# EEZ_DIB_MUX14D_r1B2.net
KiCad netlist of a schematic drawn in EAGLE
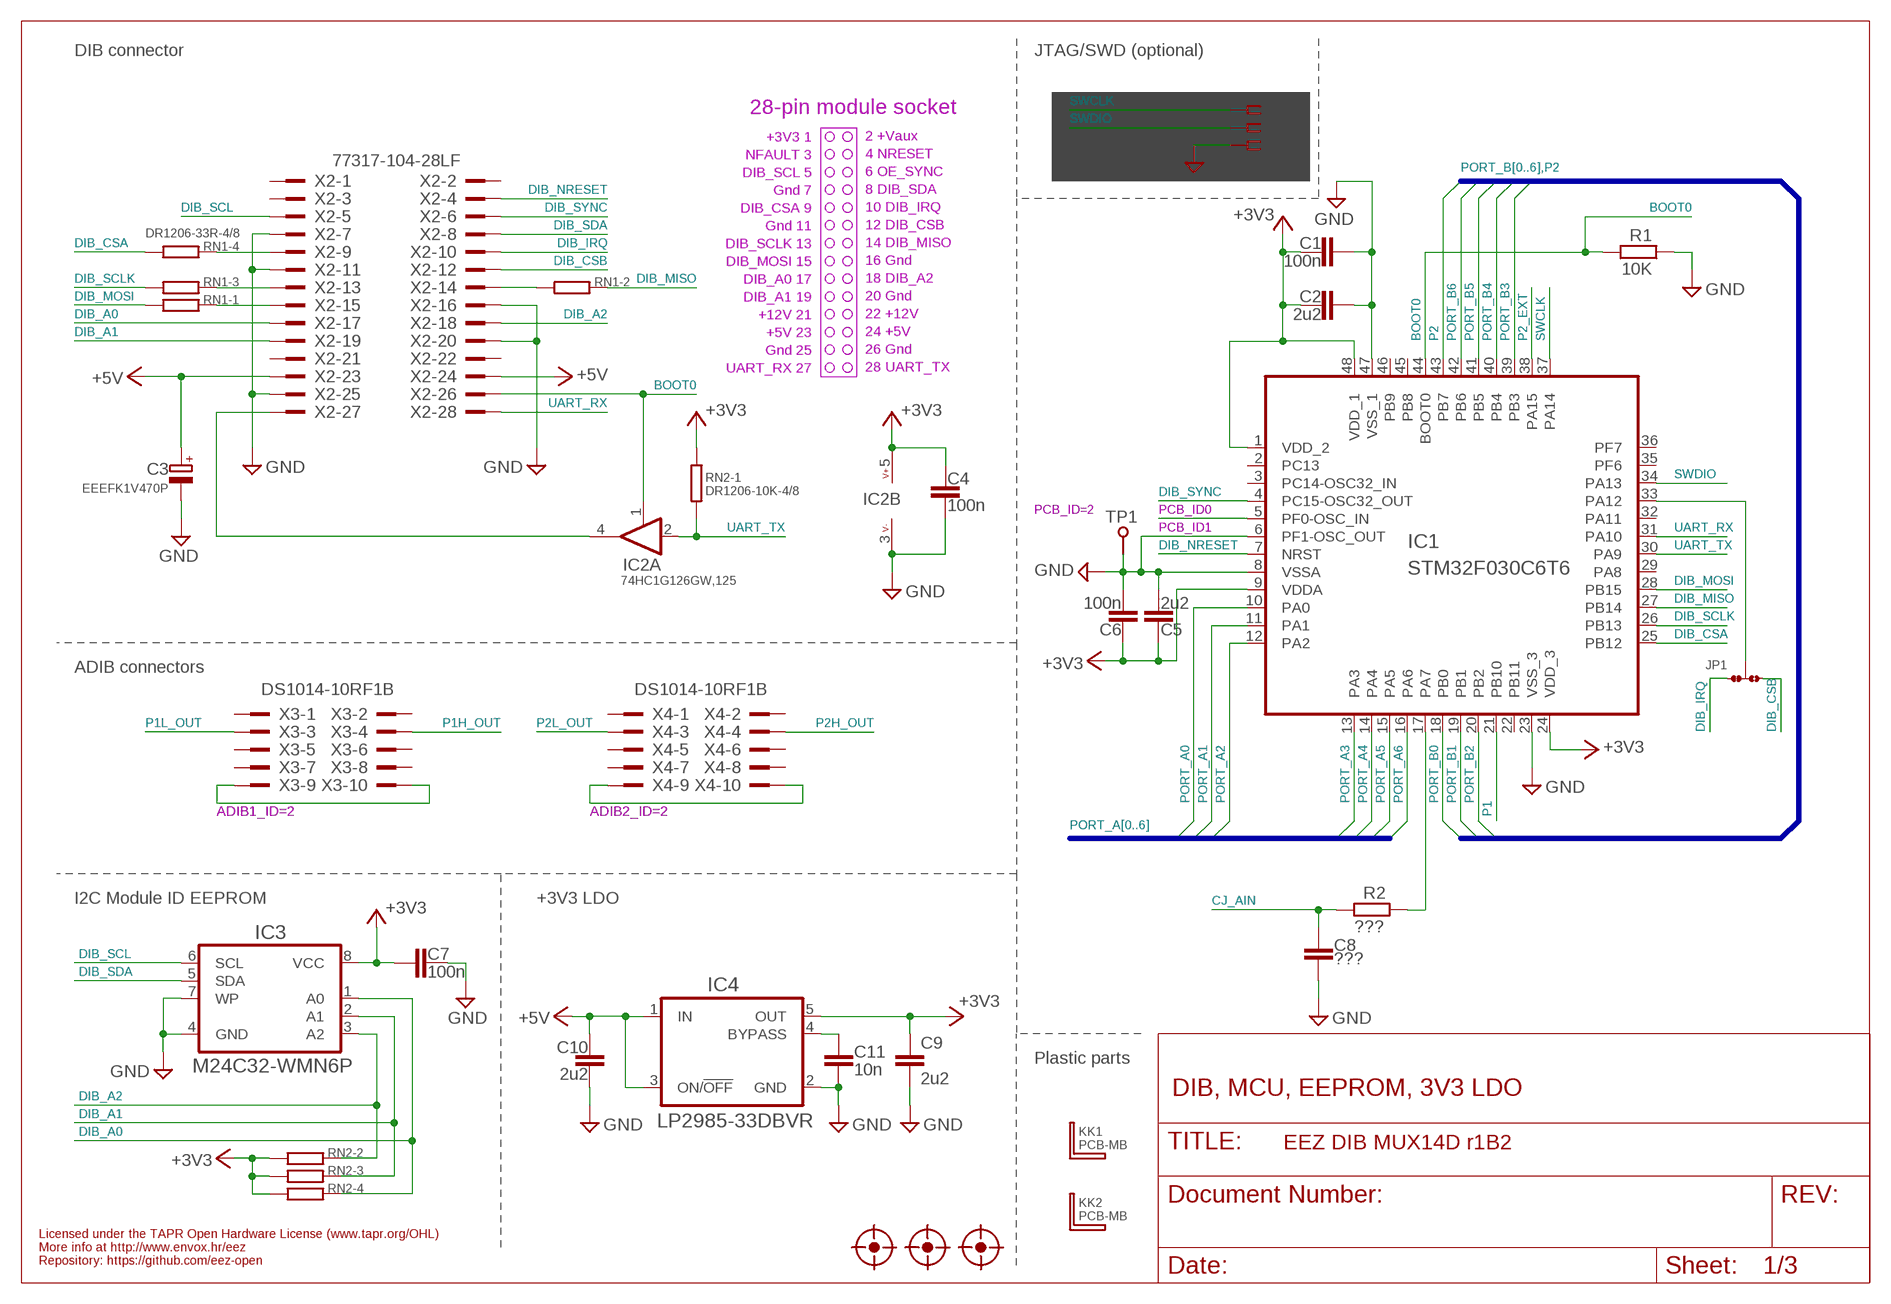
[diagram p0: schematic, sheet 1]
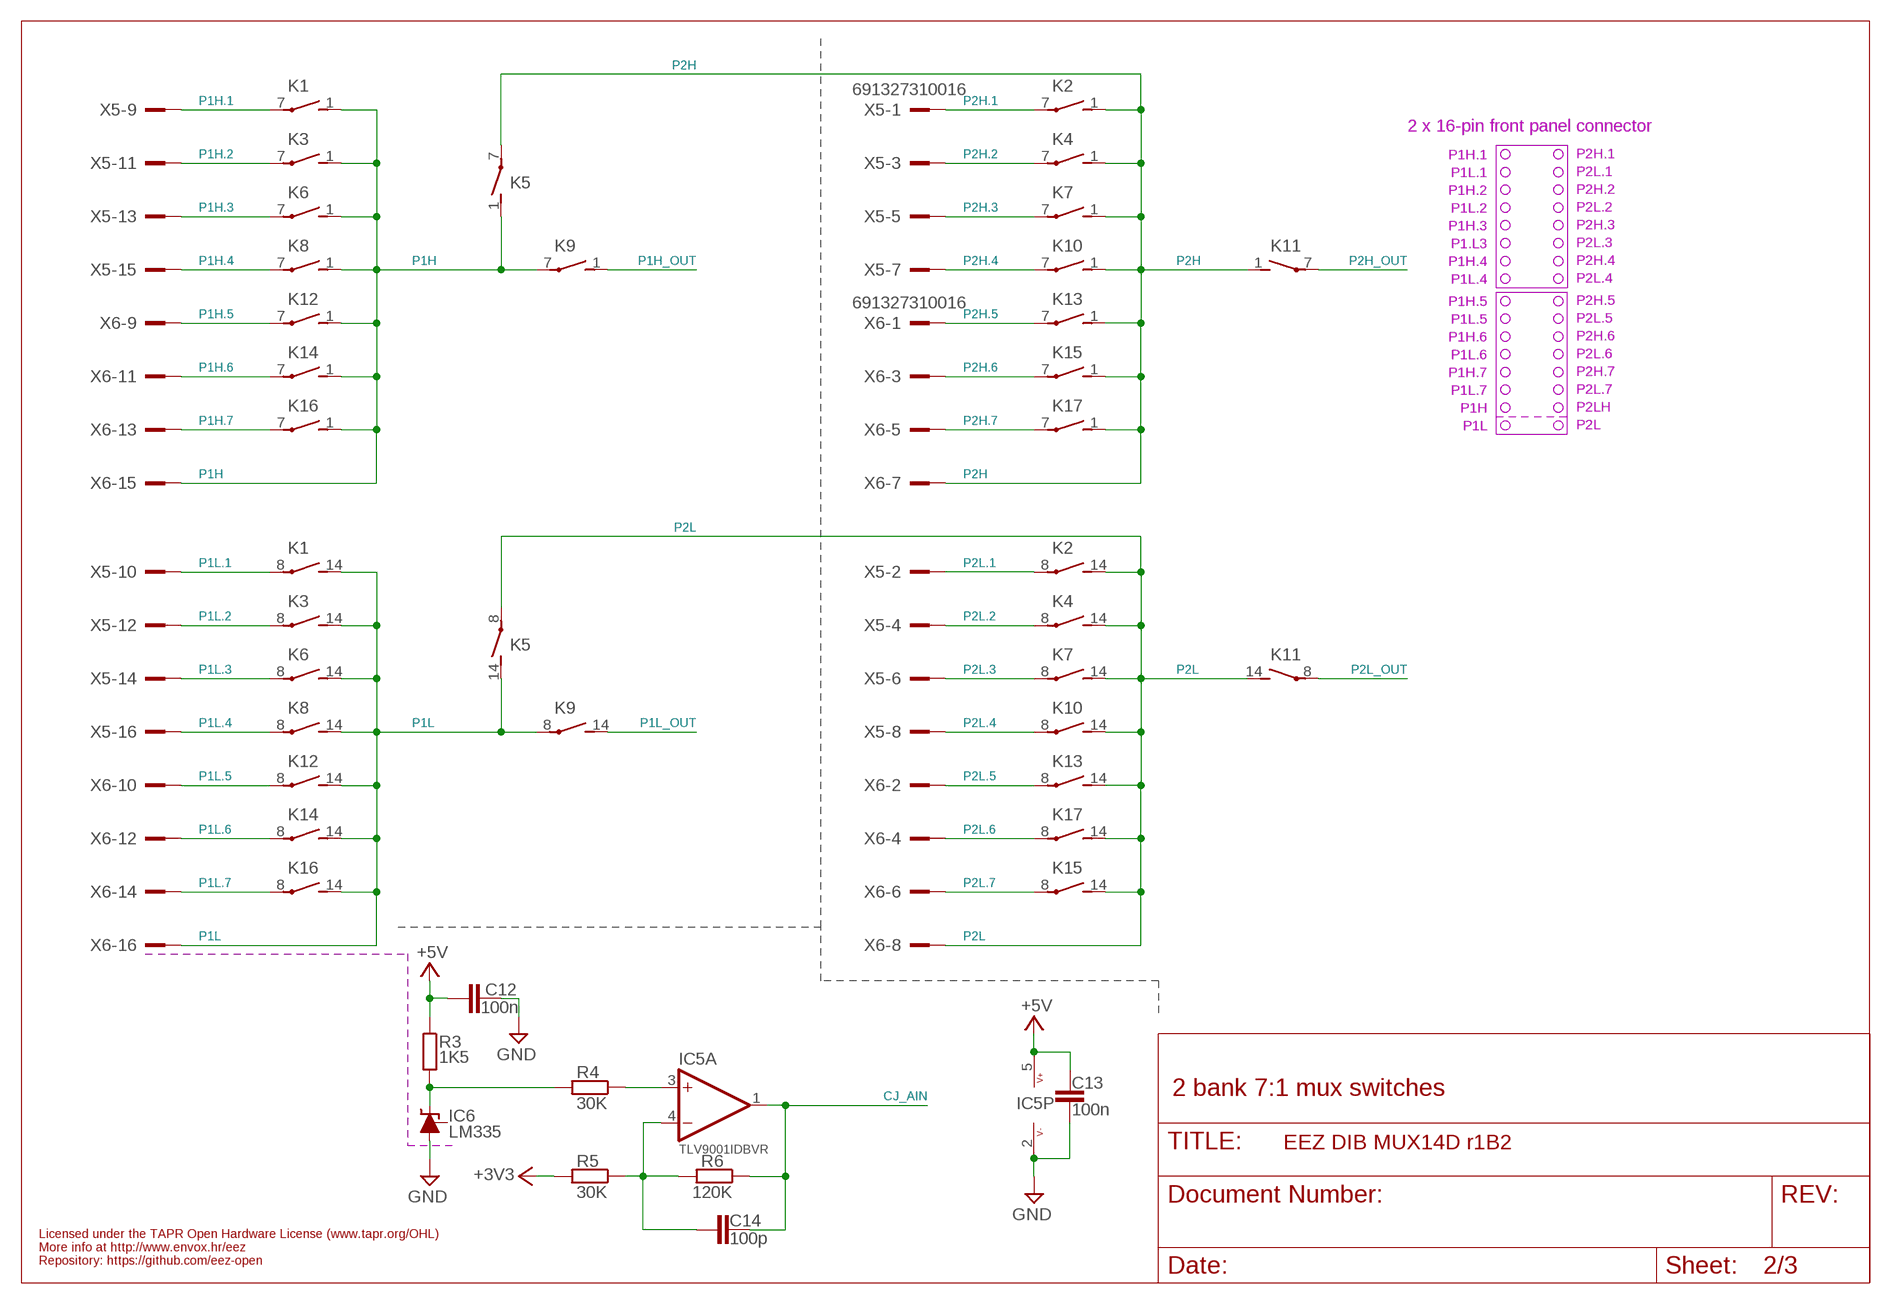
[diagram p1: schematic, sheet 2]
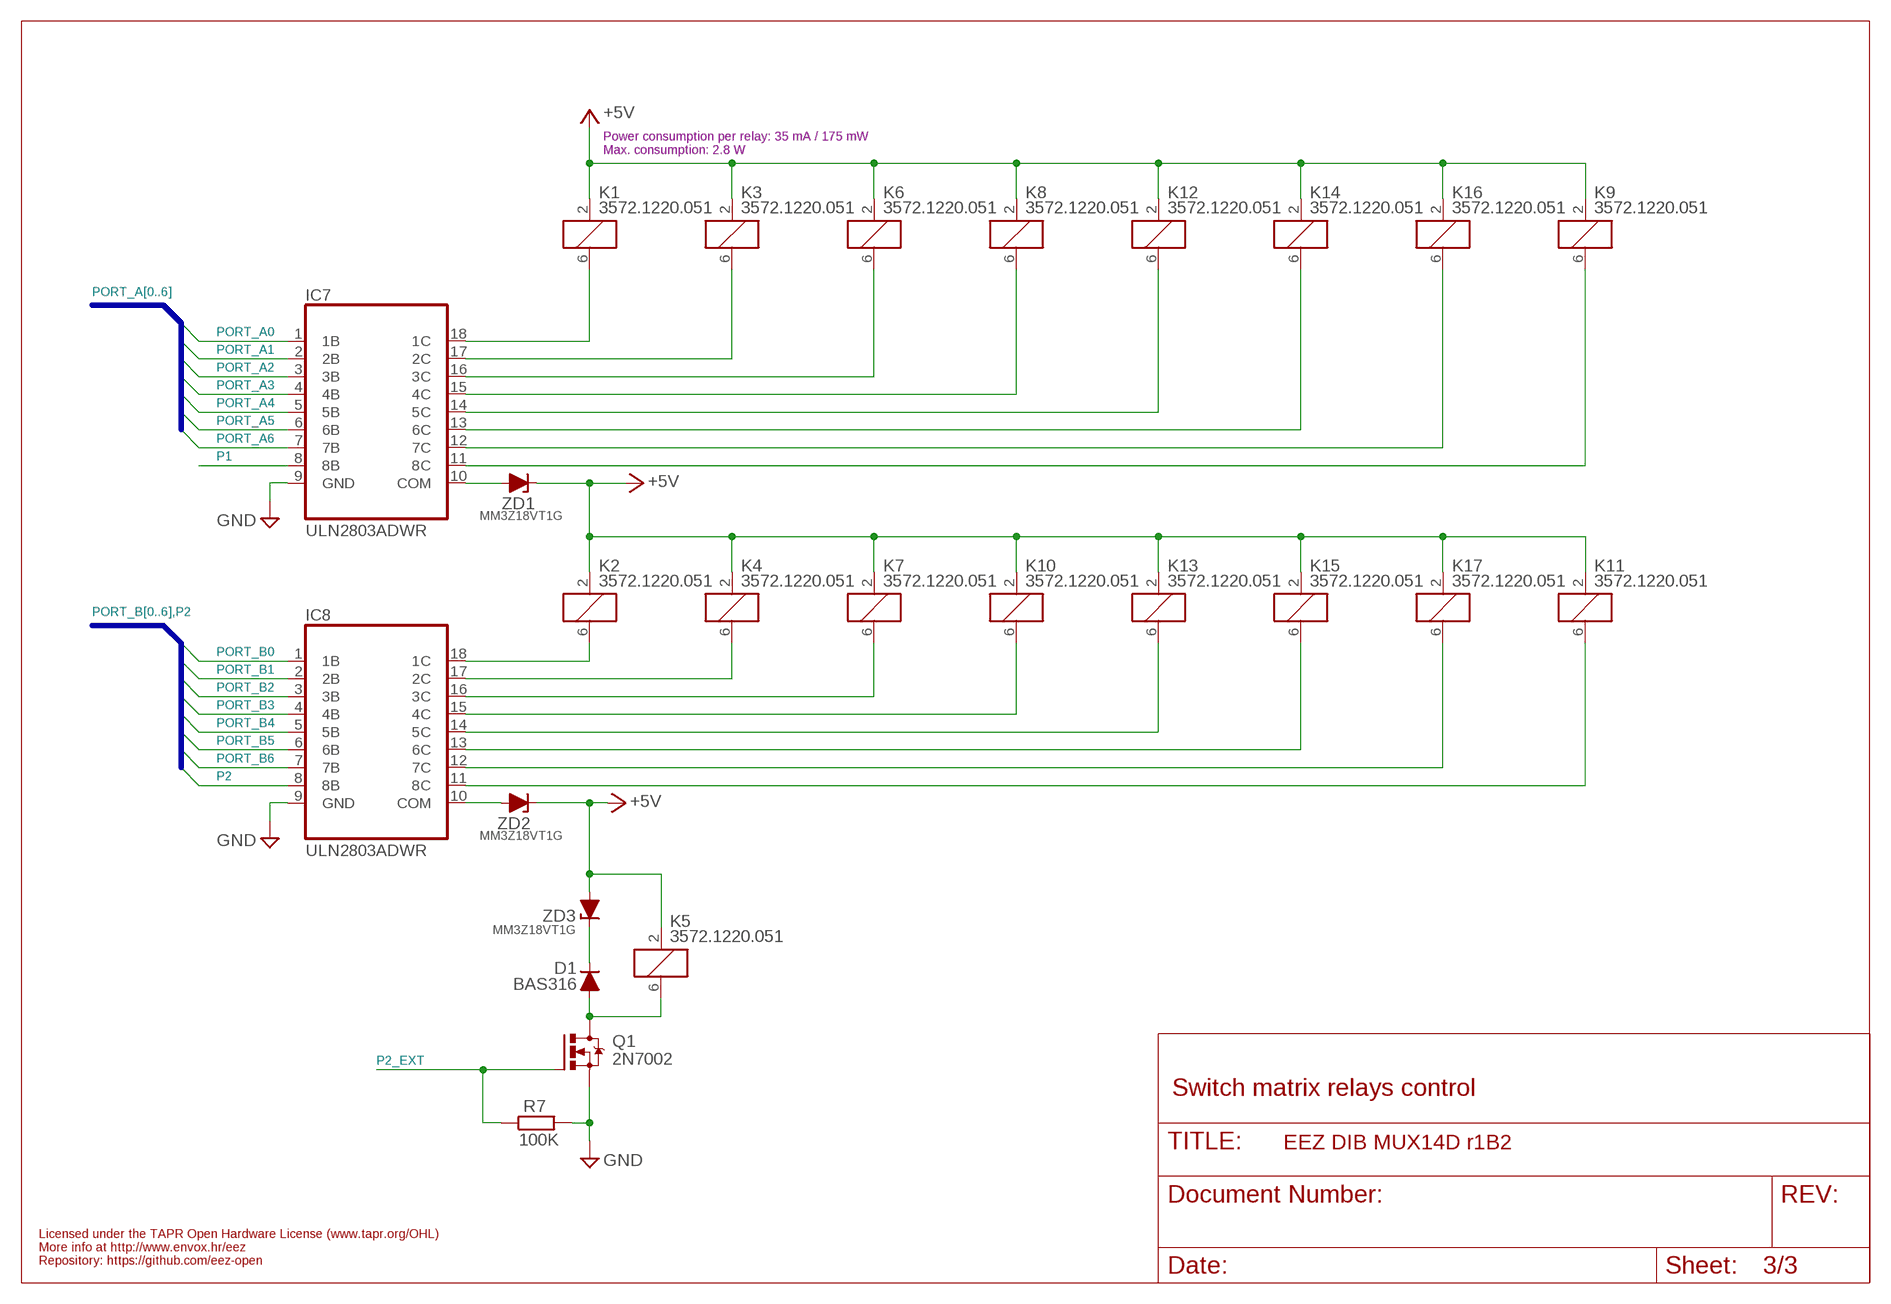
[diagram p2: schematic, sheet 3]

(export (version "E")
  (design (tool "Eeschema 10.0.6"))
  (components
    (comp (ref "C1")
      (value "100n")
      (footprint "eagle-import:C0603")
      (libsource (lib "eagle-import") (part "C-EUC0603"))
    )
    (comp (ref "C2")
      (value "2u2")
      (footprint "eagle-import:C0805")
      (libsource (lib "eagle-import") (part "C-EUC0805"))
    )
    (comp (ref "C3")
      (value "EEEFK1V470P")
      (footprint "eagle-import:CAPAE660X610N")
      (libsource (lib "eagle-import") (part "ECAPPANASONIC_H"))
    )
    (comp (ref "C4")
      (value "100n")
      (footprint "eagle-import:C0603")
      (libsource (lib "eagle-import") (part "C-EUC0603"))
    )
    (comp (ref "C5")
      (value "2u2")
      (footprint "eagle-import:C0805")
      (libsource (lib "eagle-import") (part "C-EUC0805"))
    )
    (comp (ref "C6")
      (value "100n")
      (footprint "eagle-import:C0603")
      (libsource (lib "eagle-import") (part "C-EUC0603"))
    )
    (comp (ref "C7")
      (value "100n")
      (footprint "eagle-import:C0603")
      (libsource (lib "eagle-import") (part "C-EUC0603"))
    )
    (comp (ref "C8")
      (value "???")
      (footprint "eagle-import:C0805")
      (libsource (lib "eagle-import") (part "C-EUC0805"))
    )
    (comp (ref "C9")
      (value "2u2")
      (footprint "eagle-import:C0805")
      (libsource (lib "eagle-import") (part "C-EUC0805"))
    )
    (comp (ref "C10")
      (value "2u2")
      (footprint "eagle-import:C0805")
      (libsource (lib "eagle-import") (part "C-EUC0805"))
    )
    (comp (ref "C11")
      (value "10n")
      (footprint "eagle-import:C0805")
      (libsource (lib "eagle-import") (part "C-EUC0805"))
    )
    (comp (ref "FM1")
      (value "FIDUCIAL_2")
      (footprint "eagle-import:FIDUCIAL_DUAL")
      (libsource (lib "eagle-import") (part "FIDUCIAL_2"))
    )
    (comp (ref "FM2")
      (value "FIDUCIAL_2")
      (footprint "eagle-import:FIDUCIAL_DUAL")
      (libsource (lib "eagle-import") (part "FIDUCIAL_2"))
    )
    (comp (ref "FM3")
      (value "FIDUCIAL_2")
      (footprint "eagle-import:FIDUCIAL_DUAL")
      (libsource (lib "eagle-import") (part "FIDUCIAL_2"))
    )
    (comp (ref "IC1")
      (value "STM32F030C6T6")
      (footprint "eagle-import:LQFP-48")
      (libsource (lib "eagle-import") (part "STM32F030C6T6"))
    )
    (comp (ref "IC2")
      (value "74HC1G126GW,125")
      (footprint "eagle-import:SOT65P210X110-5N")
      (libsource (lib "eagle-import") (part "74HC1G126GW,125"))
    )
    (comp (ref "IC3")
      (value "M24C32-WMN6P")
      (footprint "eagle-import:SOIC127P600X173-8N")
      (libsource (lib "eagle-import") (part "AT24CXXSOIC8"))
    )
    (comp (ref "IC4")
      (value "LP2985-33DBVR")
      (footprint "eagle-import:SOT95P270X145-5N")
      (libsource (lib "eagle-import") (part "LP2985"))
    )
    (comp (ref "JP1")
      (value "JP3-CUT-0805-ROTATED")
      (footprint "eagle-import:JP3-0805-CUT2")
      (libsource (lib "eagle-import") (part "JP3-CUT-0805-ROTATED"))
    )
    (comp (ref "KK1")
      (value "PCB-MB")
      (footprint "eagle-import:PCB-MB")
      (libsource (lib "eagle-import") (part "PCB-MB"))
    )
    (comp (ref "KK2")
      (value "PCB-MB")
      (footprint "eagle-import:PCB-MB")
      (libsource (lib "eagle-import") (part "PCB-MB"))
    )
    (comp (ref "R1")
      (value "10K")
      (footprint "eagle-import:R0805")
      (libsource (lib "eagle-import") (part "R-EU_R0805"))
    )
    (comp (ref "R2")
      (value "???")
      (footprint "eagle-import:R0805")
      (libsource (lib "eagle-import") (part "R-EU_R0805"))
    )
    (comp (ref "RN1")
      (value "DR1206-33R-4/8")
      (footprint "eagle-import:CAY16")
      (libsource (lib "eagle-import") (part "R_ARRAY4"))
    )
    (comp (ref "RN2")
      (value "DR1206-10K-4/8")
      (footprint "eagle-import:CAY16")
      (libsource (lib "eagle-import") (part "R_ARRAY4"))
    )
    (comp (ref "TP1")
      (value "PCB_TEST_TABSHIELD")
      (footprint "eagle-import:PCB_SHIELD_TAB")
      (libsource (lib "eagle-import") (part "PCB_TEST_TABSHIELD"))
    )
    (comp (ref "X1")
      (value "N.C.")
      (footprint "eagle-import:SSW-106-02-S-S")
      (fields (field (name "MPN") "SSW-106-02-S-S"))
      (libsource (lib "eagle-import") (part "SSW-106-02-S-S"))
    )
    (comp (ref "X2")
      (value "77317-104-28LF")
      (footprint "eagle-import:77317-104-28LF")
      (libsource (lib "eagle-import") (part "77317-104-28LF"))
    )
    (comp (ref "X3")
      (value "DS1014-10RF1B")
      (footprint "eagle-import:DS1014-10RF1B")
      (libsource (lib "eagle-import") (part "DS1014-10RF1B"))
    )
    (comp (ref "X4")
      (value "DS1014-10RF1B")
      (footprint "eagle-import:DS1014-10RF1B")
      (libsource (lib "eagle-import") (part "DS1014-10RF1B"))
    )
    (comp (ref "C12")
      (value "100n")
      (footprint "eagle-import:C0603")
      (libsource (lib "eagle-import") (part "C-EUC0603"))
    )
    (comp (ref "C13")
      (value "100n")
      (footprint "eagle-import:C0603")
      (libsource (lib "eagle-import") (part "C-EUC0603"))
    )
    (comp (ref "C14")
      (value "100p")
      (footprint "eagle-import:C0805")
      (libsource (lib "eagle-import") (part "C-EUC0805"))
    )
    (comp (ref "IC5")
      (value "TLV9001IDBVR")
      (footprint "eagle-import:DBV5")
      (libsource (lib "eagle-import") (part "OPA376AIDBVR"))
    )
    (comp (ref "IC6")
      (value "LM335")
      (footprint "eagle-import:TO92")
      (libsource (lib "eagle-import") (part "LM335-TO92"))
    )
    (comp (ref "K1")
      (value "3572.1220.051")
      (footprint "eagle-import:RR2A")
      (libsource (lib "eagle-import") (part "RR2A"))
    )
    (comp (ref "K2")
      (value "3572.1220.051")
      (footprint "eagle-import:RR2A")
      (libsource (lib "eagle-import") (part "RR2A"))
    )
    (comp (ref "K3")
      (value "3572.1220.051")
      (footprint "eagle-import:RR2A")
      (libsource (lib "eagle-import") (part "RR2A"))
    )
    (comp (ref "K4")
      (value "3572.1220.051")
      (footprint "eagle-import:RR2A")
      (libsource (lib "eagle-import") (part "RR2A"))
    )
    (comp (ref "K5")
      (value "3572.1220.051")
      (footprint "eagle-import:RR2A")
      (libsource (lib "eagle-import") (part "RR2A"))
    )
    (comp (ref "K6")
      (value "3572.1220.051")
      (footprint "eagle-import:RR2A")
      (libsource (lib "eagle-import") (part "RR2A"))
    )
    (comp (ref "K7")
      (value "3572.1220.051")
      (footprint "eagle-import:RR2A")
      (libsource (lib "eagle-import") (part "RR2A"))
    )
    (comp (ref "K8")
      (value "3572.1220.051")
      (footprint "eagle-import:RR2A")
      (libsource (lib "eagle-import") (part "RR2A"))
    )
    (comp (ref "K9")
      (value "3572.1220.051")
      (footprint "eagle-import:RR2A")
      (libsource (lib "eagle-import") (part "RR2A"))
    )
    (comp (ref "K10")
      (value "3572.1220.051")
      (footprint "eagle-import:RR2A")
      (libsource (lib "eagle-import") (part "RR2A"))
    )
    (comp (ref "K11")
      (value "3572.1220.051")
      (footprint "eagle-import:RR2A")
      (libsource (lib "eagle-import") (part "RR2A"))
    )
    (comp (ref "K12")
      (value "3572.1220.051")
      (footprint "eagle-import:RR2A")
      (libsource (lib "eagle-import") (part "RR2A"))
    )
    (comp (ref "K13")
      (value "3572.1220.051")
      (footprint "eagle-import:RR2A")
      (libsource (lib "eagle-import") (part "RR2A"))
    )
    (comp (ref "K14")
      (value "3572.1220.051")
      (footprint "eagle-import:RR2A")
      (libsource (lib "eagle-import") (part "RR2A"))
    )
    (comp (ref "K15")
      (value "3572.1220.051")
      (footprint "eagle-import:RR2A")
      (libsource (lib "eagle-import") (part "RR2A"))
    )
    (comp (ref "K16")
      (value "3572.1220.051")
      (footprint "eagle-import:RR2A")
      (libsource (lib "eagle-import") (part "RR2A"))
    )
    (comp (ref "K17")
      (value "3572.1220.051")
      (footprint "eagle-import:RR2A")
      (libsource (lib "eagle-import") (part "RR2A"))
    )
    (comp (ref "R3")
      (value "1K5")
      (footprint "eagle-import:R0805")
      (libsource (lib "eagle-import") (part "R-EU_R0805"))
    )
    (comp (ref "R4")
      (value "30K")
      (footprint "eagle-import:R0805")
      (libsource (lib "eagle-import") (part "R-EU_R0805"))
    )
    (comp (ref "R5")
      (value "30K")
      (footprint "eagle-import:R0805")
      (libsource (lib "eagle-import") (part "R-EU_R0805"))
    )
    (comp (ref "R6")
      (value "120K")
      (footprint "eagle-import:R0805")
      (libsource (lib "eagle-import") (part "R-EU_R0805"))
    )
    (comp (ref "X5")
      (value "691327310016")
      (footprint "eagle-import:691327310016")
      (libsource (lib "eagle-import") (part "691327310016"))
    )
    (comp (ref "X6")
      (value "691327310016")
      (footprint "eagle-import:691327310016")
      (libsource (lib "eagle-import") (part "691327310016"))
    )
    (comp (ref "D1")
      (value "BAS316")
      (footprint "eagle-import:SOD323-R")
      (libsource (lib "eagle-import") (part "DIODESOD323R"))
    )
    (comp (ref "IC7")
      (value "ULN2803ADWR")
      (footprint "eagle-import:DW18_TEX-M")
      (libsource (lib "eagle-import") (part "ULN2803ADWR"))
    )
    (comp (ref "IC8")
      (value "ULN2803ADWR")
      (footprint "eagle-import:DW18_TEX-M")
      (libsource (lib "eagle-import") (part "ULN2803ADWR"))
    )
    (comp (ref "Q1")
      (value "2N7002")
      (footprint "eagle-import:SOT103P240X110-3N")
      (fields
        (field (name "MPN") "2N7002-7-F")
        (field (name "MPN_1") "2N7002-7-F")
        (field (name "OC_FARNELL") "1713823")
        (field (name "OC_NEWARK") "25R5679")
        (field (name "PACKAGE") "SOT-23-3")
        (field (name "SUPPLIER") "DIODES INC.")
      )
      (libsource (lib "eagle-import") (part "2N7002"))
    )
    (comp (ref "R7")
      (value "100K")
      (footprint "eagle-import:R0805")
      (libsource (lib "eagle-import") (part "R-EU_R0805"))
    )
    (comp (ref "ZD1")
      (value "MM3Z18VT1G")
      (footprint "eagle-import:SOD323-R")
      (libsource (lib "eagle-import") (part "ZENER-DIODESOD323R"))
    )
    (comp (ref "ZD2")
      (value "MM3Z18VT1G")
      (footprint "eagle-import:SOD323-R")
      (libsource (lib "eagle-import") (part "ZENER-DIODESOD323R"))
    )
    (comp (ref "ZD3")
      (value "MM3Z18VT1G")
      (footprint "eagle-import:SOD323-R")
      (libsource (lib "eagle-import") (part "ZENER-DIODESOD323R"))
    )
  )
  (nets
    (net (code "1") (name "+3V3") (class "Default")
      (node (ref "C1") (pin "2") (pinfunction "2_2") (pintype "passive"))
      (node (ref "C2") (pin "1") (pinfunction "1_1") (pintype "passive"))
      (node (ref "C4") (pin "1") (pinfunction "1_1") (pintype "passive"))
      (node (ref "C5") (pin "2") (pinfunction "2_2") (pintype "passive"))
      (node (ref "C6") (pin "1") (pinfunction "1_1") (pintype "passive"))
      (node (ref "C7") (pin "2") (pinfunction "2_2") (pintype "passive"))
      (node (ref "C9") (pin "1") (pinfunction "1_1") (pintype "passive"))
      (node (ref "IC1") (pin "1") (pinfunction "VDD_2_1") (pintype "passive"))
      (node (ref "IC1") (pin "24") (pinfunction "VDD_3_24") (pintype "passive"))
      (node (ref "IC1") (pin "48") (pinfunction "VDD_1_48") (pintype "passive"))
      (node (ref "IC1") (pin "9") (pinfunction "VDDA_9") (pintype "passive"))
      (node (ref "IC2") (pin "5") (pinfunction "V+_5") (pintype "power_in"))
      (node (ref "IC3") (pin "8") (pinfunction "VCC_8") (pintype "power_in"))
      (node (ref "IC4") (pin "5") (pinfunction "OUT_5") (pintype "passive"))
      (node (ref "R5") (pin "2") (pinfunction "2_2") (pintype "passive"))
      (node (ref "RN2") (pin "5") (pinfunction "2_5") (pintype "passive"))
      (node (ref "RN2") (pin "6") (pinfunction "2_6") (pintype "passive"))
      (node (ref "RN2") (pin "7") (pinfunction "2_7") (pintype "passive"))
      (node (ref "RN2") (pin "8") (pinfunction "2_8") (pintype "passive"))
    )
    (net (code "2") (name "+5V") (class "Default")
      (node (ref "C10") (pin "2") (pinfunction "2_2") (pintype "passive"))
      (node (ref "C12") (pin "1") (pinfunction "1_1") (pintype "passive"))
      (node (ref "C13") (pin "1") (pinfunction "1_1") (pintype "passive"))
      (node (ref "C3") (pin "1") (pinfunction "+_1") (pintype "passive"))
      (node (ref "IC4") (pin "1") (pinfunction "IN_1") (pintype "input"))
      (node (ref "IC4") (pin "3") (pinfunction "ON/~{OFF}_3") (pintype "input"))
      (node (ref "IC5") (pin "5") (pinfunction "V+_5") (pintype "power_in"))
      (node (ref "K1") (pin "2") (pinfunction "1_2") (pintype "passive"))
      (node (ref "K10") (pin "2") (pinfunction "1_2") (pintype "passive"))
      (node (ref "K11") (pin "2") (pinfunction "1_2") (pintype "passive"))
      (node (ref "K12") (pin "2") (pinfunction "1_2") (pintype "passive"))
      (node (ref "K13") (pin "2") (pinfunction "1_2") (pintype "passive"))
      (node (ref "K14") (pin "2") (pinfunction "1_2") (pintype "passive"))
      (node (ref "K15") (pin "2") (pinfunction "1_2") (pintype "passive"))
      (node (ref "K16") (pin "2") (pinfunction "1_2") (pintype "passive"))
      (node (ref "K17") (pin "2") (pinfunction "1_2") (pintype "passive"))
      (node (ref "K2") (pin "2") (pinfunction "1_2") (pintype "passive"))
      (node (ref "K3") (pin "2") (pinfunction "1_2") (pintype "passive"))
      (node (ref "K4") (pin "2") (pinfunction "1_2") (pintype "passive"))
      (node (ref "K5") (pin "2") (pinfunction "1_2") (pintype "passive"))
      (node (ref "K6") (pin "2") (pinfunction "1_2") (pintype "passive"))
      (node (ref "K7") (pin "2") (pinfunction "1_2") (pintype "passive"))
      (node (ref "K8") (pin "2") (pinfunction "1_2") (pintype "passive"))
      (node (ref "K9") (pin "2") (pinfunction "1_2") (pintype "passive"))
      (node (ref "R3") (pin "1") (pinfunction "1_1") (pintype "passive"))
      (node (ref "X2") (pin "23") (pinfunction "1_23") (pintype "passive"))
      (node (ref "X2") (pin "24") (pinfunction "1_24") (pintype "passive"))
      (node (ref "ZD1") (pin "C") (pinfunction "C_C") (pintype "passive"))
      (node (ref "ZD2") (pin "C") (pinfunction "C_C") (pintype "passive"))
      (node (ref "ZD3") (pin "A") (pinfunction "A_A") (pintype "passive"))
    )
    (net (code "7") (name "BOOT0") (class "Default")
      (node (ref "IC1") (pin "44") (pinfunction "BOOT0_44") (pintype "input"))
      (node (ref "IC2") (pin "1") (pinfunction "EN_1") (pintype "input"))
      (node (ref "R1") (pin "2") (pinfunction "2_2") (pintype "passive"))
      (node (ref "X2") (pin "26") (pinfunction "1_26") (pintype "passive"))
    )
    (net (code "8") (name "CJ_AIN") (class "Default")
      (node (ref "C14") (pin "2") (pinfunction "2_2") (pintype "passive"))
      (node (ref "C8") (pin "2") (pinfunction "2_2") (pintype "passive"))
      (node (ref "IC5") (pin "1") (pinfunction "OUT_1") (pintype "output"))
      (node (ref "R2") (pin "2") (pinfunction "2_2") (pintype "passive"))
      (node (ref "R6") (pin "1") (pinfunction "1_1") (pintype "passive"))
    )
    (net (code "9") (name "DIB_A0") (class "Default")
      (node (ref "IC3") (pin "1") (pinfunction "A0_1") (pintype "input"))
      (node (ref "RN2") (pin "4") (pinfunction "1_4") (pintype "passive"))
      (node (ref "X2") (pin "17") (pinfunction "1_17") (pintype "passive"))
    )
    (net (code "10") (name "DIB_A1") (class "Default")
      (node (ref "IC3") (pin "2") (pinfunction "A1_2") (pintype "input"))
      (node (ref "RN2") (pin "3") (pinfunction "1_3") (pintype "passive"))
      (node (ref "X2") (pin "19") (pinfunction "1_19") (pintype "passive"))
    )
    (net (code "11") (name "DIB_A2") (class "Default")
      (node (ref "IC3") (pin "3") (pinfunction "A2_3") (pintype "input"))
      (node (ref "RN2") (pin "2") (pinfunction "1_2") (pintype "passive"))
      (node (ref "X2") (pin "18") (pinfunction "1_18") (pintype "passive"))
    )
    (net (code "12") (name "DIB_CSA") (class "Default")
      (node (ref "IC1") (pin "25") (pinfunction "PB12_25") (pintype "bidirectional"))
      (node (ref "RN1") (pin "4") (pinfunction "1_4") (pintype "passive"))
    )
    (net (code "13") (name "DIB_CSB") (class "Default")
      (node (ref "JP1") (pin "NO") (pinfunction "NO_NO") (pintype "passive"))
      (node (ref "X2") (pin "12") (pinfunction "1_12") (pintype "passive"))
    )
    (net (code "14") (name "DIB_IRQ") (class "Default")
      (node (ref "JP1") (pin "NC") (pinfunction "NC_NC") (pintype "passive"))
      (node (ref "X2") (pin "10") (pinfunction "1_10") (pintype "passive"))
    )
    (net (code "15") (name "DIB_MISO") (class "Default")
      (node (ref "IC1") (pin "27") (pinfunction "PB14_27") (pintype "bidirectional"))
      (node (ref "RN1") (pin "2") (pinfunction "1_2") (pintype "passive"))
    )
    (net (code "16") (name "DIB_MOSI") (class "Default")
      (node (ref "IC1") (pin "28") (pinfunction "PB15_28") (pintype "bidirectional"))
      (node (ref "RN1") (pin "1") (pinfunction "1_1") (pintype "passive"))
    )
    (net (code "17") (name "DIB_NRESET") (class "Default")
      (node (ref "IC1") (pin "7") (pinfunction "NRST_7") (pintype "input"))
      (node (ref "X2") (pin "4") (pinfunction "1_4") (pintype "passive"))
    )
    (net (code "18") (name "DIB_SCL") (class "Default")
      (node (ref "IC3") (pin "6") (pinfunction "SCL_6") (pintype "bidirectional"))
      (node (ref "X2") (pin "5") (pinfunction "1_5") (pintype "passive"))
    )
    (net (code "19") (name "DIB_SCLK") (class "Default")
      (node (ref "IC1") (pin "26") (pinfunction "PB13_26") (pintype "bidirectional"))
      (node (ref "RN1") (pin "3") (pinfunction "1_3") (pintype "passive"))
    )
    (net (code "20") (name "DIB_SDA") (class "Default")
      (node (ref "IC3") (pin "5") (pinfunction "SDA_5") (pintype "bidirectional"))
      (node (ref "X2") (pin "8") (pinfunction "1_8") (pintype "passive"))
    )
    (net (code "21") (name "DIB_SYNC") (class "Default")
      (node (ref "IC1") (pin "4") (pinfunction "PC15-OSC32_OUT_4") (pintype "bidirectional"))
      (node (ref "X2") (pin "6") (pinfunction "1_6") (pintype "passive"))
    )
    (net (code "22") (name "GND") (class "Default")
      (node (ref "C1") (pin "1") (pinfunction "1_1") (pintype "passive"))
      (node (ref "C10") (pin "1") (pinfunction "1_1") (pintype "passive"))
      (node (ref "C11") (pin "1") (pinfunction "1_1") (pintype "passive"))
      (node (ref "C12") (pin "2") (pinfunction "2_2") (pintype "passive"))
      (node (ref "C13") (pin "2") (pinfunction "2_2") (pintype "passive"))
      (node (ref "C2") (pin "2") (pinfunction "2_2") (pintype "passive"))
      (node (ref "C3") (pin "2") (pinfunction "-_2") (pintype "passive"))
      (node (ref "C4") (pin "2") (pinfunction "2_2") (pintype "passive"))
      (node (ref "C5") (pin "1") (pinfunction "1_1") (pintype "passive"))
      (node (ref "C6") (pin "2") (pinfunction "2_2") (pintype "passive"))
      (node (ref "C7") (pin "1") (pinfunction "1_1") (pintype "passive"))
      (node (ref "C8") (pin "1") (pinfunction "1_1") (pintype "passive"))
      (node (ref "C9") (pin "2") (pinfunction "2_2") (pintype "passive"))
      (node (ref "IC1") (pin "23") (pinfunction "VSS_3_23") (pintype "passive"))
      (node (ref "IC1") (pin "47") (pinfunction "VSS_1_47") (pintype "passive"))
      (node (ref "IC1") (pin "6") (pinfunction "PF1-OSC_OUT_6") (pintype "bidirectional"))
      (node (ref "IC1") (pin "8") (pinfunction "VSSA_8") (pintype "passive"))
      (node (ref "IC2") (pin "3") (pinfunction "V-_3") (pintype "power_in"))
      (node (ref "IC3") (pin "4") (pinfunction "GND_4") (pintype "passive"))
      (node (ref "IC3") (pin "7") (pinfunction "WP_7") (pintype "input"))
      (node (ref "IC4") (pin "2") (pinfunction "GND_2") (pintype "passive"))
      (node (ref "IC5") (pin "2") (pinfunction "V-_2") (pintype "power_in"))
      (node (ref "IC6") (pin "3") (pinfunction "A_3") (pintype "passive"))
      (node (ref "IC7") (pin "9") (pinfunction "GND_9") (pintype "input"))
      (node (ref "IC8") (pin "9") (pinfunction "GND_9") (pintype "input"))
      (node (ref "Q1") (pin "2") (pinfunction "S_2") (pintype "passive"))
      (node (ref "R1") (pin "1") (pinfunction "1_1") (pintype "passive"))
      (node (ref "R7") (pin "2") (pinfunction "2_2") (pintype "passive"))
      (node (ref "TP1") (pin "1") (pinfunction "P$1_1") (pintype "bidirectional"))
      (node (ref "X1") (pin "3") (pinfunction "1_3") (pintype "passive"))
      (node (ref "X2") (pin "11") (pinfunction "1_11") (pintype "passive"))
      (node (ref "X2") (pin "16") (pinfunction "1_16") (pintype "passive"))
      (node (ref "X2") (pin "20") (pinfunction "1_20") (pintype "passive"))
      (node (ref "X2") (pin "25") (pinfunction "1_25") (pintype "passive"))
      (node (ref "X2") (pin "7") (pinfunction "1_7") (pintype "passive"))
    )
    (net (code "23") (name "Net-(D1-PadC)") (class "Default")
      (node (ref "D1") (pin "C") (pinfunction "C_C") (pintype "passive"))
      (node (ref "ZD3") (pin "C") (pinfunction "C_C") (pintype "passive"))
    )
    (net (code "24") (name "Net-(IC1-PA7)") (class "Default")
      (node (ref "IC1") (pin "17") (pinfunction "PA7_17") (pintype "bidirectional"))
      (node (ref "R2") (pin "1") (pinfunction "1_1") (pintype "passive"))
    )
    (net (code "25") (name "Net-(IC1-PA12)") (class "Default")
      (node (ref "IC1") (pin "33") (pinfunction "PA12_33") (pintype "bidirectional"))
      (node (ref "JP1") (pin "COM") (pinfunction "COM_COM") (pintype "passive"))
    )
    (net (code "26") (name "Net-(IC2A-O)") (class "Default")
      (node (ref "IC2") (pin "4") (pinfunction "O_4") (pintype "output"))
      (node (ref "X2") (pin "27") (pinfunction "1_27") (pintype "passive"))
    )
    (net (code "27") (name "Net-(IC4-BYPASS)") (class "Default")
      (node (ref "C11") (pin "2") (pinfunction "2_2") (pintype "passive"))
      (node (ref "IC4") (pin "4") (pinfunction "BYPASS_4") (pintype "passive"))
    )
    (net (code "28") (name "Net-(IC5A-+IN)") (class "Default")
      (node (ref "IC5") (pin "3") (pinfunction "+IN_3") (pintype "input"))
      (node (ref "R4") (pin "1") (pinfunction "1_1") (pintype "passive"))
    )
    (net (code "29") (name "Net-(IC5A--IN)") (class "Default")
      (node (ref "C14") (pin "1") (pinfunction "1_1") (pintype "passive"))
      (node (ref "IC5") (pin "4") (pinfunction "-IN_4") (pintype "input"))
      (node (ref "R5") (pin "1") (pinfunction "1_1") (pintype "passive"))
      (node (ref "R6") (pin "2") (pinfunction "2_2") (pintype "passive"))
    )
    (net (code "30") (name "Net-(IC6-C)") (class "Default")
      (node (ref "IC6") (pin "2") (pinfunction "C_2") (pintype "passive"))
      (node (ref "R3") (pin "2") (pinfunction "2_2") (pintype "passive"))
      (node (ref "R4") (pin "2") (pinfunction "2_2") (pintype "passive"))
    )
    (net (code "31") (name "Net-(IC7-1C)") (class "Default")
      (node (ref "IC7") (pin "18") (pinfunction "1C_18") (pintype "output"))
      (node (ref "K1") (pin "6") (pinfunction "2_6") (pintype "passive"))
    )
    (net (code "32") (name "Net-(IC7-2C)") (class "Default")
      (node (ref "IC7") (pin "17") (pinfunction "2C_17") (pintype "output"))
      (node (ref "K3") (pin "6") (pinfunction "2_6") (pintype "passive"))
    )
    (net (code "33") (name "Net-(IC7-3C)") (class "Default")
      (node (ref "IC7") (pin "16") (pinfunction "3C_16") (pintype "output"))
      (node (ref "K6") (pin "6") (pinfunction "2_6") (pintype "passive"))
    )
    (net (code "34") (name "Net-(IC7-4C)") (class "Default")
      (node (ref "IC7") (pin "15") (pinfunction "4C_15") (pintype "output"))
      (node (ref "K8") (pin "6") (pinfunction "2_6") (pintype "passive"))
    )
    (net (code "35") (name "Net-(IC7-5C)") (class "Default")
      (node (ref "IC7") (pin "14") (pinfunction "5C_14") (pintype "output"))
      (node (ref "K12") (pin "6") (pinfunction "2_6") (pintype "passive"))
    )
    (net (code "36") (name "Net-(IC7-6C)") (class "Default")
      (node (ref "IC7") (pin "13") (pinfunction "6C_13") (pintype "output"))
      (node (ref "K14") (pin "6") (pinfunction "2_6") (pintype "passive"))
    )
    (net (code "37") (name "Net-(IC7-7C)") (class "Default")
      (node (ref "IC7") (pin "12") (pinfunction "7C_12") (pintype "output"))
      (node (ref "K16") (pin "6") (pinfunction "2_6") (pintype "passive"))
    )
    (net (code "38") (name "Net-(IC7-8C)") (class "Default")
      (node (ref "IC7") (pin "11") (pinfunction "8C_11") (pintype "output"))
      (node (ref "K9") (pin "6") (pinfunction "2_6") (pintype "passive"))
    )
    (net (code "39") (name "Net-(IC7-COM)") (class "Default")
      (node (ref "IC7") (pin "10") (pinfunction "COM_10") (pintype "passive"))
      (node (ref "ZD1") (pin "A") (pinfunction "A_A") (pintype "passive"))
    )
    (net (code "40") (name "Net-(IC8-1C)") (class "Default")
      (node (ref "IC8") (pin "18") (pinfunction "1C_18") (pintype "output"))
      (node (ref "K2") (pin "6") (pinfunction "2_6") (pintype "passive"))
    )
    (net (code "41") (name "Net-(IC8-2C)") (class "Default")
      (node (ref "IC8") (pin "17") (pinfunction "2C_17") (pintype "output"))
      (node (ref "K4") (pin "6") (pinfunction "2_6") (pintype "passive"))
    )
    (net (code "42") (name "Net-(IC8-3C)") (class "Default")
      (node (ref "IC8") (pin "16") (pinfunction "3C_16") (pintype "output"))
      (node (ref "K7") (pin "6") (pinfunction "2_6") (pintype "passive"))
    )
    (net (code "43") (name "Net-(IC8-4C)") (class "Default")
      (node (ref "IC8") (pin "15") (pinfunction "4C_15") (pintype "output"))
      (node (ref "K10") (pin "6") (pinfunction "2_6") (pintype "passive"))
    )
    (net (code "44") (name "Net-(IC8-5C)") (class "Default")
      (node (ref "IC8") (pin "14") (pinfunction "5C_14") (pintype "output"))
      (node (ref "K13") (pin "6") (pinfunction "2_6") (pintype "passive"))
    )
    (net (code "45") (name "Net-(IC8-6C)") (class "Default")
      (node (ref "IC8") (pin "13") (pinfunction "6C_13") (pintype "output"))
      (node (ref "K15") (pin "6") (pinfunction "2_6") (pintype "passive"))
    )
    (net (code "46") (name "Net-(IC8-7C)") (class "Default")
      (node (ref "IC8") (pin "12") (pinfunction "7C_12") (pintype "output"))
      (node (ref "K17") (pin "6") (pinfunction "2_6") (pintype "passive"))
    )
    (net (code "47") (name "Net-(IC8-8C)") (class "Default")
      (node (ref "IC8") (pin "11") (pinfunction "8C_11") (pintype "output"))
      (node (ref "K11") (pin "6") (pinfunction "2_6") (pintype "passive"))
    )
    (net (code "48") (name "Net-(IC8-COM)") (class "Default")
      (node (ref "IC8") (pin "10") (pinfunction "COM_10") (pintype "passive"))
      (node (ref "ZD2") (pin "A") (pinfunction "A_A") (pintype "passive"))
    )
    (net (code "49") (name "Net-(K5A-2)") (class "Default")
      (node (ref "D1") (pin "A") (pinfunction "A_A") (pintype "passive"))
      (node (ref "K5") (pin "6") (pinfunction "2_6") (pintype "passive"))
      (node (ref "Q1") (pin "3") (pinfunction "D_3") (pintype "passive"))
    )
    (net (code "50") (name "Net-(RN1A-2)") (class "Default")
      (node (ref "RN1") (pin "8") (pinfunction "2_8") (pintype "passive"))
      (node (ref "X2") (pin "15") (pinfunction "1_15") (pintype "passive"))
    )
    (net (code "51") (name "Net-(RN1B-2)") (class "Default")
      (node (ref "RN1") (pin "7") (pinfunction "2_7") (pintype "passive"))
      (node (ref "X2") (pin "14") (pinfunction "1_14") (pintype "passive"))
    )
    (net (code "52") (name "Net-(RN1C-2)") (class "Default")
      (node (ref "RN1") (pin "6") (pinfunction "2_6") (pintype "passive"))
      (node (ref "X2") (pin "13") (pinfunction "1_13") (pintype "passive"))
    )
    (net (code "53") (name "Net-(RN1D-2)") (class "Default")
      (node (ref "RN1") (pin "5") (pinfunction "2_5") (pintype "passive"))
      (node (ref "X2") (pin "9") (pinfunction "1_9") (pintype "passive"))
    )
    (net (code "54") (name "Net-(X3B-1)") (class "Default")
      (node (ref "X3") (pin "10") (pinfunction "1_10") (pintype "passive"))
      (node (ref "X3") (pin "9") (pinfunction "1_9") (pintype "passive"))
    )
    (net (code "55") (name "Net-(X4B-1)") (class "Default")
      (node (ref "X4") (pin "10") (pinfunction "1_10") (pintype "passive"))
      (node (ref "X4") (pin "9") (pinfunction "1_9") (pintype "passive"))
    )
    (net (code "56") (name "P1") (class "Default")
      (node (ref "IC1") (pin "21") (pinfunction "PB10_21") (pintype "bidirectional"))
      (node (ref "IC7") (pin "8") (pinfunction "8B_8") (pintype "input"))
    )
    (net (code "57") (name "P1H") (class "Default")
      (node (ref "K1") (pin "1") (pinfunction "S_1") (pintype "passive"))
      (node (ref "K12") (pin "1") (pinfunction "S_1") (pintype "passive"))
      (node (ref "K14") (pin "1") (pinfunction "S_1") (pintype "passive"))
      (node (ref "K16") (pin "1") (pinfunction "S_1") (pintype "passive"))
      (node (ref "K3") (pin "1") (pinfunction "S_1") (pintype "passive"))
      (node (ref "K5") (pin "1") (pinfunction "S_1") (pintype "passive"))
      (node (ref "K6") (pin "1") (pinfunction "S_1") (pintype "passive"))
      (node (ref "K8") (pin "1") (pinfunction "S_1") (pintype "passive"))
      (node (ref "K9") (pin "7") (pinfunction "P_7") (pintype "passive"))
      (node (ref "X6") (pin "15") (pinfunction "1_15") (pintype "passive"))
    )
    (net (code "58") (name "P1H.1") (class "Default")
      (node (ref "K1") (pin "7") (pinfunction "P_7") (pintype "passive"))
      (node (ref "X5") (pin "9") (pinfunction "1_9") (pintype "passive"))
    )
    (net (code "59") (name "P1H.2") (class "Default")
      (node (ref "K3") (pin "7") (pinfunction "P_7") (pintype "passive"))
      (node (ref "X5") (pin "11") (pinfunction "1_11") (pintype "passive"))
    )
    (net (code "60") (name "P1H.3") (class "Default")
      (node (ref "K6") (pin "7") (pinfunction "P_7") (pintype "passive"))
      (node (ref "X5") (pin "13") (pinfunction "1_13") (pintype "passive"))
    )
    (net (code "61") (name "P1H.4") (class "Default")
      (node (ref "K8") (pin "7") (pinfunction "P_7") (pintype "passive"))
      (node (ref "X5") (pin "15") (pinfunction "1_15") (pintype "passive"))
    )
    (net (code "62") (name "P1H.5") (class "Default")
      (node (ref "K12") (pin "7") (pinfunction "P_7") (pintype "passive"))
      (node (ref "X6") (pin "9") (pinfunction "1_9") (pintype "passive"))
    )
    (net (code "63") (name "P1H.6") (class "Default")
      (node (ref "K14") (pin "7") (pinfunction "P_7") (pintype "passive"))
      (node (ref "X6") (pin "11") (pinfunction "1_11") (pintype "passive"))
    )
    (net (code "64") (name "P1H.7") (class "Default")
      (node (ref "K16") (pin "7") (pinfunction "P_7") (pintype "passive"))
      (node (ref "X6") (pin "13") (pinfunction "1_13") (pintype "passive"))
    )
    (net (code "65") (name "P1H_OUT") (class "Default")
      (node (ref "K9") (pin "1") (pinfunction "S_1") (pintype "passive"))
      (node (ref "X3") (pin "4") (pinfunction "1_4") (pintype "passive"))
    )
    (net (code "66") (name "P1L") (class "Default")
      (node (ref "K1") (pin "14") (pinfunction "S_14") (pintype "passive"))
      (node (ref "K12") (pin "14") (pinfunction "S_14") (pintype "passive"))
      (node (ref "K14") (pin "14") (pinfunction "S_14") (pintype "passive"))
      (node (ref "K16") (pin "14") (pinfunction "S_14") (pintype "passive"))
      (node (ref "K3") (pin "14") (pinfunction "S_14") (pintype "passive"))
      (node (ref "K5") (pin "14") (pinfunction "S_14") (pintype "passive"))
      (node (ref "K6") (pin "14") (pinfunction "S_14") (pintype "passive"))
      (node (ref "K8") (pin "14") (pinfunction "S_14") (pintype "passive"))
      (node (ref "K9") (pin "8") (pinfunction "P_8") (pintype "passive"))
      (node (ref "X6") (pin "16") (pinfunction "1_16") (pintype "passive"))
    )
    (net (code "67") (name "P1L.1") (class "Default")
      (node (ref "K1") (pin "8") (pinfunction "P_8") (pintype "passive"))
      (node (ref "X5") (pin "10") (pinfunction "1_10") (pintype "passive"))
    )
    (net (code "68") (name "P1L.2") (class "Default")
      (node (ref "K3") (pin "8") (pinfunction "P_8") (pintype "passive"))
      (node (ref "X5") (pin "12") (pinfunction "1_12") (pintype "passive"))
    )
    (net (code "69") (name "P1L.3") (class "Default")
      (node (ref "K6") (pin "8") (pinfunction "P_8") (pintype "passive"))
      (node (ref "X5") (pin "14") (pinfunction "1_14") (pintype "passive"))
    )
    (net (code "70") (name "P1L.4") (class "Default")
      (node (ref "K8") (pin "8") (pinfunction "P_8") (pintype "passive"))
      (node (ref "X5") (pin "16") (pinfunction "1_16") (pintype "passive"))
    )
    (net (code "71") (name "P1L.5") (class "Default")
      (node (ref "K12") (pin "8") (pinfunction "P_8") (pintype "passive"))
      (node (ref "X6") (pin "10") (pinfunction "1_10") (pintype "passive"))
    )
    (net (code "72") (name "P1L.6") (class "Default")
      (node (ref "K14") (pin "8") (pinfunction "P_8") (pintype "passive"))
      (node (ref "X6") (pin "12") (pinfunction "1_12") (pintype "passive"))
    )
    (net (code "73") (name "P1L.7") (class "Default")
      (node (ref "K16") (pin "8") (pinfunction "P_8") (pintype "passive"))
      (node (ref "X6") (pin "14") (pinfunction "1_14") (pintype "passive"))
    )
    (net (code "74") (name "P1L_OUT") (class "Default")
      (node (ref "K9") (pin "14") (pinfunction "S_14") (pintype "passive"))
      (node (ref "X3") (pin "3") (pinfunction "1_3") (pintype "passive"))
    )
    (net (code "75") (name "P2") (class "Default")
      (node (ref "IC1") (pin "43") (pinfunction "PB7_43") (pintype "bidirectional"))
      (node (ref "IC8") (pin "8") (pinfunction "8B_8") (pintype "input"))
    )
    (net (code "76") (name "P2H") (class "Default")
      (node (ref "K10") (pin "1") (pinfunction "S_1") (pintype "passive"))
      (node (ref "K11") (pin "1") (pinfunction "S_1") (pintype "passive"))
      (node (ref "K13") (pin "1") (pinfunction "S_1") (pintype "passive"))
      (node (ref "K15") (pin "1") (pinfunction "S_1") (pintype "passive"))
      (node (ref "K17") (pin "1") (pinfunction "S_1") (pintype "passive"))
      (node (ref "K2") (pin "1") (pinfunction "S_1") (pintype "passive"))
      (node (ref "K4") (pin "1") (pinfunction "S_1") (pintype "passive"))
      (node (ref "K5") (pin "7") (pinfunction "P_7") (pintype "passive"))
      (node (ref "K7") (pin "1") (pinfunction "S_1") (pintype "passive"))
      (node (ref "X6") (pin "7") (pinfunction "1_7") (pintype "passive"))
    )
    (net (code "77") (name "P2H.1") (class "Default")
      (node (ref "K2") (pin "7") (pinfunction "P_7") (pintype "passive"))
      (node (ref "X5") (pin "1") (pinfunction "1_1") (pintype "passive"))
    )
    (net (code "78") (name "P2H.2") (class "Default")
      (node (ref "K4") (pin "7") (pinfunction "P_7") (pintype "passive"))
      (node (ref "X5") (pin "3") (pinfunction "1_3") (pintype "passive"))
    )
    (net (code "79") (name "P2H.3") (class "Default")
      (node (ref "K7") (pin "7") (pinfunction "P_7") (pintype "passive"))
      (node (ref "X5") (pin "5") (pinfunction "1_5") (pintype "passive"))
    )
    (net (code "80") (name "P2H.4") (class "Default")
      (node (ref "K10") (pin "7") (pinfunction "P_7") (pintype "passive"))
      (node (ref "X5") (pin "7") (pinfunction "1_7") (pintype "passive"))
    )
    (net (code "81") (name "P2H.5") (class "Default")
      (node (ref "K13") (pin "7") (pinfunction "P_7") (pintype "passive"))
      (node (ref "X6") (pin "1") (pinfunction "1_1") (pintype "passive"))
    )
    (net (code "82") (name "P2H.6") (class "Default")
      (node (ref "K15") (pin "7") (pinfunction "P_7") (pintype "passive"))
      (node (ref "X6") (pin "3") (pinfunction "1_3") (pintype "passive"))
    )
    (net (code "83") (name "P2H.7") (class "Default")
      (node (ref "K17") (pin "7") (pinfunction "P_7") (pintype "passive"))
      (node (ref "X6") (pin "5") (pinfunction "1_5") (pintype "passive"))
    )
    (net (code "84") (name "P2H_OUT") (class "Default")
      (node (ref "K11") (pin "7") (pinfunction "P_7") (pintype "passive"))
      (node (ref "X4") (pin "4") (pinfunction "1_4") (pintype "passive"))
    )
    (net (code "85") (name "P2L") (class "Default")
      (node (ref "K10") (pin "14") (pinfunction "S_14") (pintype "passive"))
      (node (ref "K11") (pin "14") (pinfunction "S_14") (pintype "passive"))
      (node (ref "K13") (pin "14") (pinfunction "S_14") (pintype "passive"))
      (node (ref "K15") (pin "14") (pinfunction "S_14") (pintype "passive"))
      (node (ref "K17") (pin "14") (pinfunction "S_14") (pintype "passive"))
      (node (ref "K2") (pin "14") (pinfunction "S_14") (pintype "passive"))
      (node (ref "K4") (pin "14") (pinfunction "S_14") (pintype "passive"))
      (node (ref "K5") (pin "8") (pinfunction "P_8") (pintype "passive"))
      (node (ref "K7") (pin "14") (pinfunction "S_14") (pintype "passive"))
      (node (ref "X6") (pin "8") (pinfunction "1_8") (pintype "passive"))
    )
    (net (code "86") (name "P2L.1") (class "Default")
      (node (ref "K2") (pin "8") (pinfunction "P_8") (pintype "passive"))
      (node (ref "X5") (pin "2") (pinfunction "1_2") (pintype "passive"))
    )
    (net (code "87") (name "P2L.2") (class "Default")
      (node (ref "K4") (pin "8") (pinfunction "P_8") (pintype "passive"))
      (node (ref "X5") (pin "4") (pinfunction "1_4") (pintype "passive"))
    )
    (net (code "88") (name "P2L.3") (class "Default")
      (node (ref "K7") (pin "8") (pinfunction "P_8") (pintype "passive"))
      (node (ref "X5") (pin "6") (pinfunction "1_6") (pintype "passive"))
    )
    (net (code "89") (name "P2L.4") (class "Default")
      (node (ref "K10") (pin "8") (pinfunction "P_8") (pintype "passive"))
      (node (ref "X5") (pin "8") (pinfunction "1_8") (pintype "passive"))
    )
    (net (code "90") (name "P2L.5") (class "Default")
      (node (ref "K13") (pin "8") (pinfunction "P_8") (pintype "passive"))
      (node (ref "X6") (pin "2") (pinfunction "1_2") (pintype "passive"))
    )
    (net (code "91") (name "P2L.6") (class "Default")
      (node (ref "K17") (pin "8") (pinfunction "P_8") (pintype "passive"))
      (node (ref "X6") (pin "4") (pinfunction "1_4") (pintype "passive"))
    )
    (net (code "92") (name "P2L.7") (class "Default")
      (node (ref "K15") (pin "8") (pinfunction "P_8") (pintype "passive"))
      (node (ref "X6") (pin "6") (pinfunction "1_6") (pintype "passive"))
    )
    (net (code "93") (name "P2L_OUT") (class "Default")
      (node (ref "K11") (pin "8") (pinfunction "P_8") (pintype "passive"))
      (node (ref "X4") (pin "3") (pinfunction "1_3") (pintype "passive"))
    )
    (net (code "94") (name "P2_EXT") (class "Default")
      (node (ref "IC1") (pin "38") (pinfunction "PA15_38") (pintype "bidirectional"))
      (node (ref "Q1") (pin "1") (pinfunction "G_1") (pintype "passive"))
      (node (ref "R7") (pin "1") (pinfunction "1_1") (pintype "passive"))
    )
    (net (code "95") (name "PORT_A0") (class "Default")
      (node (ref "IC1") (pin "10") (pinfunction "PA0_10") (pintype "bidirectional"))
      (node (ref "IC7") (pin "1") (pinfunction "1B_1") (pintype "input"))
    )
    (net (code "96") (name "PORT_A1") (class "Default")
      (node (ref "IC1") (pin "11") (pinfunction "PA1_11") (pintype "bidirectional"))
      (node (ref "IC7") (pin "2") (pinfunction "2B_2") (pintype "input"))
    )
    (net (code "97") (name "PORT_A2") (class "Default")
      (node (ref "IC1") (pin "12") (pinfunction "PA2_12") (pintype "bidirectional"))
      (node (ref "IC7") (pin "3") (pinfunction "3B_3") (pintype "input"))
    )
    (net (code "98") (name "PORT_A3") (class "Default")
      (node (ref "IC1") (pin "13") (pinfunction "PA3_13") (pintype "bidirectional"))
      (node (ref "IC7") (pin "4") (pinfunction "4B_4") (pintype "input"))
    )
    (net (code "99") (name "PORT_A4") (class "Default")
      (node (ref "IC1") (pin "14") (pinfunction "PA4_14") (pintype "bidirectional"))
      (node (ref "IC7") (pin "5") (pinfunction "5B_5") (pintype "input"))
    )
    (net (code "100") (name "PORT_A5") (class "Default")
      (node (ref "IC1") (pin "15") (pinfunction "PA5_15") (pintype "bidirectional"))
      (node (ref "IC7") (pin "6") (pinfunction "6B_6") (pintype "input"))
    )
    (net (code "101") (name "PORT_A6") (class "Default")
      (node (ref "IC1") (pin "16") (pinfunction "PA6_16") (pintype "bidirectional"))
      (node (ref "IC7") (pin "7") (pinfunction "7B_7") (pintype "input"))
    )
    (net (code "102") (name "PORT_B0") (class "Default")
      (node (ref "IC1") (pin "18") (pinfunction "PB0_18") (pintype "bidirectional"))
      (node (ref "IC8") (pin "1") (pinfunction "1B_1") (pintype "input"))
    )
    (net (code "103") (name "PORT_B1") (class "Default")
      (node (ref "IC1") (pin "19") (pinfunction "PB1_19") (pintype "bidirectional"))
      (node (ref "IC8") (pin "2") (pinfunction "2B_2") (pintype "input"))
    )
    (net (code "104") (name "PORT_B2") (class "Default")
      (node (ref "IC1") (pin "20") (pinfunction "PB2_20") (pintype "bidirectional"))
      (node (ref "IC8") (pin "3") (pinfunction "3B_3") (pintype "input"))
    )
    (net (code "105") (name "PORT_B3") (class "Default")
      (node (ref "IC1") (pin "39") (pinfunction "PB3_39") (pintype "bidirectional"))
      (node (ref "IC8") (pin "4") (pinfunction "4B_4") (pintype "input"))
    )
    (net (code "106") (name "PORT_B4") (class "Default")
      (node (ref "IC1") (pin "40") (pinfunction "PB4_40") (pintype "bidirectional"))
      (node (ref "IC8") (pin "5") (pinfunction "5B_5") (pintype "input"))
    )
    (net (code "107") (name "PORT_B5") (class "Default")
      (node (ref "IC1") (pin "41") (pinfunction "PB5_41") (pintype "bidirectional"))
      (node (ref "IC8") (pin "6") (pinfunction "6B_6") (pintype "input"))
    )
    (net (code "108") (name "PORT_B6") (class "Default")
      (node (ref "IC1") (pin "42") (pinfunction "PB6_42") (pintype "bidirectional"))
      (node (ref "IC8") (pin "7") (pinfunction "7B_7") (pintype "input"))
    )
    (net (code "109") (name "SWCLK") (class "Default")
      (node (ref "IC1") (pin "37") (pinfunction "PA14_37") (pintype "bidirectional"))
      (node (ref "X1") (pin "2") (pinfunction "1_2") (pintype "passive"))
    )
    (net (code "110") (name "SWDIO") (class "Default")
      (node (ref "IC1") (pin "34") (pinfunction "PA13_34") (pintype "bidirectional"))
      (node (ref "X1") (pin "4") (pinfunction "1_4") (pintype "passive"))
    )
    (net (code "111") (name "UART_RX") (class "Default")
      (node (ref "IC1") (pin "31") (pinfunction "PA10_31") (pintype "bidirectional"))
      (node (ref "X2") (pin "28") (pinfunction "1_28") (pintype "passive"))
    )
    (net (code "112") (name "UART_TX") (class "Default")
      (node (ref "IC1") (pin "30") (pinfunction "PA9_30") (pintype "bidirectional"))
      (node (ref "IC2") (pin "2") (pinfunction "I_2") (pintype "input"))
      (node (ref "RN2") (pin "1") (pinfunction "1_1") (pintype "passive"))
    )
    (net (code "113") (name "unconnected-(IC1-PA8-Pad29)") (class "Default")
      (node (ref "IC1") (pin "29") (pinfunction "PA8_29") (pintype "bidirectional"))
    )
    (net (code "114") (name "unconnected-(IC1-PA11-Pad32)") (class "Default")
      (node (ref "IC1") (pin "32") (pinfunction "PA11_32") (pintype "bidirectional"))
    )
    (net (code "115") (name "unconnected-(IC1-PB8-Pad45)") (class "Default")
      (node (ref "IC1") (pin "45") (pinfunction "PB8_45") (pintype "bidirectional"))
    )
    (net (code "116") (name "unconnected-(IC1-PB9-Pad46)") (class "Default")
      (node (ref "IC1") (pin "46") (pinfunction "PB9_46") (pintype "bidirectional"))
    )
    (net (code "117") (name "unconnected-(IC1-PB11-Pad22)") (class "Default")
      (node (ref "IC1") (pin "22") (pinfunction "PB11_22") (pintype "bidirectional"))
    )
    (net (code "118") (name "unconnected-(IC1-PC13-Pad2)") (class "Default")
      (node (ref "IC1") (pin "2") (pinfunction "PC13_2") (pintype "bidirectional"))
    )
    (net (code "119") (name "unconnected-(IC1-PC14-OSC32_IN-Pad3)") (class "Default")
      (node (ref "IC1") (pin "3") (pinfunction "PC14-OSC32_IN_3") (pintype "bidirectional"))
    )
    (net (code "120") (name "unconnected-(IC1-PF0-OSC_IN-Pad5)") (class "Default")
      (node (ref "IC1") (pin "5") (pinfunction "PF0-OSC_IN_5") (pintype "bidirectional"))
    )
    (net (code "121") (name "unconnected-(IC1-PF6-Pad35)") (class "Default")
      (node (ref "IC1") (pin "35") (pinfunction "PF6_35") (pintype "bidirectional"))
    )
    (net (code "122") (name "unconnected-(IC1-PF7-Pad36)") (class "Default")
      (node (ref "IC1") (pin "36") (pinfunction "PF7_36") (pintype "bidirectional"))
    )
    (net (code "123") (name "unconnected-(IC6-ADJ-Pad1)") (class "Default")
      (node (ref "IC6") (pin "1") (pinfunction "ADJ_1") (pintype "passive"))
    )
    (net (code "124") (name "unconnected-(X2-Pad1)") (class "Default")
      (node (ref "X2") (pin "1") (pinfunction "1_1") (pintype "passive"))
    )
    (net (code "125") (name "unconnected-(X2L-1-Pad2)") (class "Default")
      (node (ref "X2") (pin "2") (pinfunction "1_2") (pintype "passive"))
    )
    (net (code "126") (name "unconnected-(X2N-1-Pad21)") (class "Default")
      (node (ref "X2") (pin "21") (pinfunction "1_21") (pintype "passive"))
    )
    (net (code "127") (name "unconnected-(X2O-1-Pad22)") (class "Default")
      (node (ref "X2") (pin "22") (pinfunction "1_22") (pintype "passive"))
    )
    (net (code "128") (name "unconnected-(X2V-1-Pad3)") (class "Default")
      (node (ref "X2") (pin "3") (pinfunction "1_3") (pintype "passive"))
    )
    (net (code "129") (name "unconnected-(X3-Pad1)") (class "Default")
      (node (ref "X3") (pin "1") (pinfunction "1_1") (pintype "passive"))
    )
    (net (code "130") (name "unconnected-(X3C-1-Pad2)") (class "Default")
      (node (ref "X3") (pin "2") (pinfunction "1_2") (pintype "passive"))
    )
    (net (code "131") (name "unconnected-(X3F-1-Pad5)") (class "Default")
      (node (ref "X3") (pin "5") (pinfunction "1_5") (pintype "passive"))
    )
    (net (code "132") (name "unconnected-(X3G-1-Pad6)") (class "Default")
      (node (ref "X3") (pin "6") (pinfunction "1_6") (pintype "passive"))
    )
    (net (code "133") (name "unconnected-(X3H-1-Pad7)") (class "Default")
      (node (ref "X3") (pin "7") (pinfunction "1_7") (pintype "passive"))
    )
    (net (code "134") (name "unconnected-(X3I-1-Pad8)") (class "Default")
      (node (ref "X3") (pin "8") (pinfunction "1_8") (pintype "passive"))
    )
    (net (code "135") (name "unconnected-(X4-Pad1)") (class "Default")
      (node (ref "X4") (pin "1") (pinfunction "1_1") (pintype "passive"))
    )
    (net (code "136") (name "unconnected-(X4C-1-Pad2)") (class "Default")
      (node (ref "X4") (pin "2") (pinfunction "1_2") (pintype "passive"))
    )
    (net (code "137") (name "unconnected-(X4F-1-Pad5)") (class "Default")
      (node (ref "X4") (pin "5") (pinfunction "1_5") (pintype "passive"))
    )
    (net (code "138") (name "unconnected-(X4G-1-Pad6)") (class "Default")
      (node (ref "X4") (pin "6") (pinfunction "1_6") (pintype "passive"))
    )
    (net (code "139") (name "unconnected-(X4H-1-Pad7)") (class "Default")
      (node (ref "X4") (pin "7") (pinfunction "1_7") (pintype "passive"))
    )
    (net (code "140") (name "unconnected-(X4I-1-Pad8)") (class "Default")
      (node (ref "X4") (pin "8") (pinfunction "1_8") (pintype "passive"))
    )
  )
)
